# MissingLink.net
KiCad netlist of a schematic drawn in Altium Designer
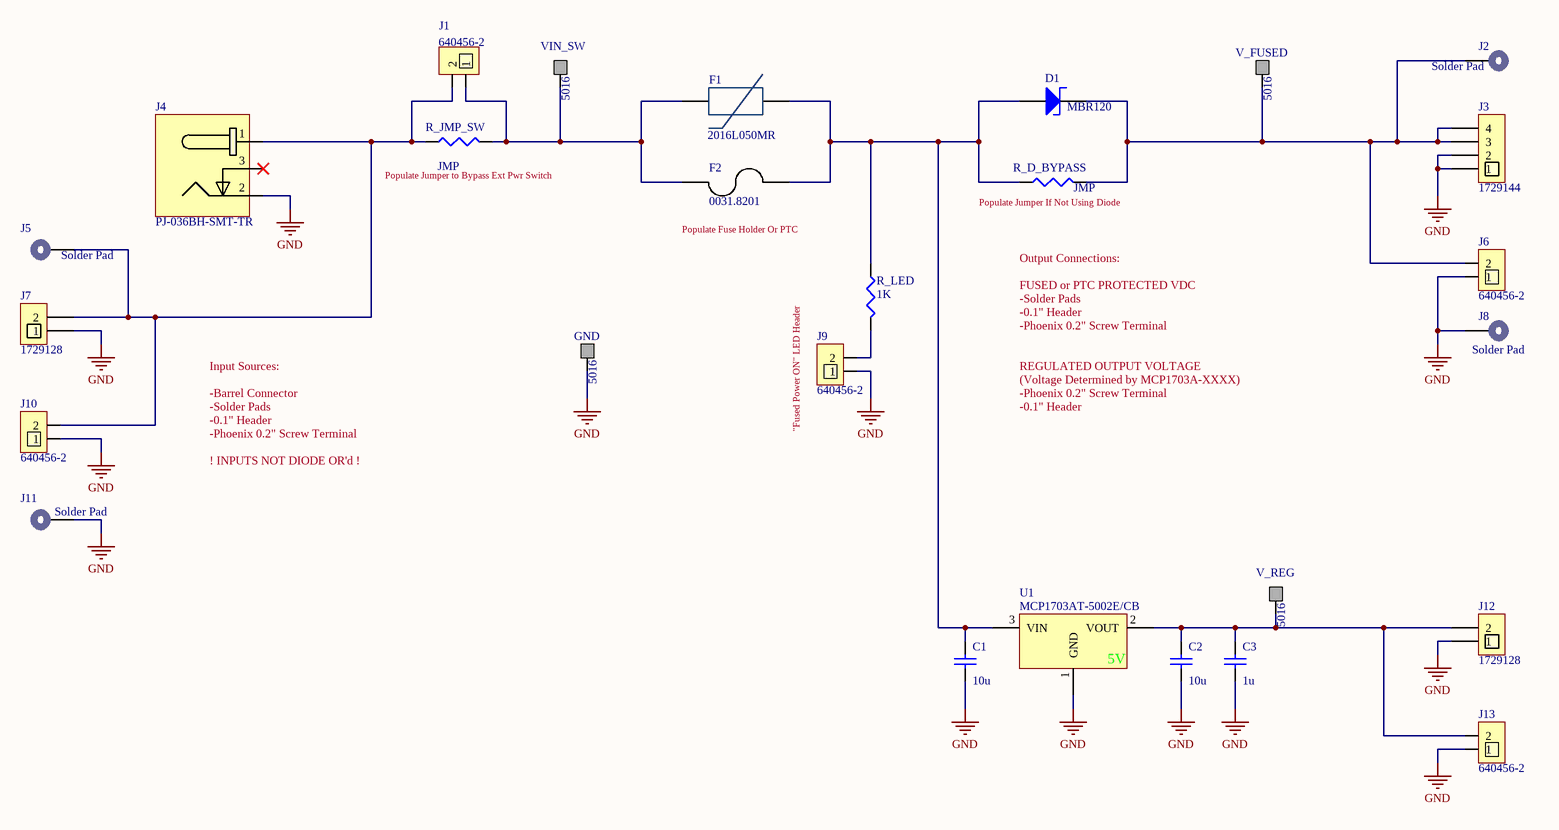
[diagram p0: MissingLink.SchDoc]

(export (version "E")
  (design (tool "Eeschema 10.0.6"))
  (components
    (comp (ref "C1")
      (value "10u")
      (footprint "C1206")
      (description "Capacitor (Semiconductor SIM Model)")
      (fields (field (name "Comment") "Cap Semi") (field (name "PUBLISHER") "Altium Limited"))
      (libsource (lib "Miscellaneous Devices") (part "Cap Semi"))
    )
    (comp (ref "C2")
      (value "10u")
      (footprint "C1206")
      (description "Capacitor (Semiconductor SIM Model)")
      (fields (field (name "Comment") "Cap Semi") (field (name "PUBLISHER") "Altium Limited"))
      (libsource (lib "Miscellaneous Devices") (part "Cap Semi"))
    )
    (comp (ref "C3")
      (value "1u")
      (footprint "C1206")
      (description "Capacitor (Semiconductor SIM Model)")
      (fields (field (name "Comment") "Cap Semi") (field (name "PUBLISHER") "Altium Limited"))
      (libsource (lib "Miscellaneous Devices") (part "Cap Semi"))
    )
    (comp (ref "D1")
      (value "Diode")
      (footprint "SOD-123FL")
      (description "DIODE SCHOTTKY 20V 1A SOD123FL")
      (fields
        (field (name "MANUFACTURER") "ON Semiconductor")
        (field (name "MANUFACTURER PART NUMBER") "MBR120")
      )
      (libsource (lib "Electric_Ray_Integrated_01SEPT2018") (part "MBR120"))
    )
    (comp (ref "F1")
      (value "2016L050MR")
      (footprint "PolyFuse_2016L")
      (description "600mA PTC")
      (fields (field (name "MANUFACTURER") "Littelfuse Inc."))
      (libsource (lib "Electric_Ray_Integrated_01SEPT2018") (part "PTC_2016L050MR_LITTELFUSE"))
    )
    (comp (ref "F2")
      (value "0031.8201")
      (footprint "0031.8201")
      (description "FUSE BLOK CARTRIDGE 500V 10A PCB")
      (fields (field (name "MANUFACTURER") "Schurter"))
      (libsource (lib "Electric_Ray_Integrated_01SEPT2018") (part "0031.8201"))
    )
    (comp (ref "GND")
      (value "5016")
      (footprint "5016")
      (description "PC TEST POINT COMPACT SMD")
      (fields (field (name "MANUFACTURER") "Keystone Electronics"))
      (libsource (lib "Electric_Ray_Integrated_01SEPT2018") (part "5016"))
    )
    (comp (ref "J1")
      (value "640456-2")
      (footprint "640456-2")
      (description "CONN HEADER VERT 2POS .100 TIN")
      (fields (field (name "MANUFACTURER") "TE Connectivity AMP Connectors"))
      (libsource (lib "") (part "640456-2_2"))
    )
    (comp (ref "J2")
      (value "Solder Pad")
      (footprint "61mil_Solder_Hole")
      (description "A Solderable Pad")
      (libsource (lib "Electric_Ray_Integrated_01SEPT2018") (part "Solderable_Hole"))
    )
    (comp (ref "J3")
      (value "1729144")
      (footprint "1729144_PHX_4")
      (description "CONN TERM BLOCK 4POS 5.08MM PCB")
      (fields (field (name "MANUFACTURER") "Phoenix Connect"))
      (libsource (lib "Electric_Ray_Integrated_01SEPT2018") (part "1729144"))
    )
    (comp (ref "J4")
      (value "PJ-036BH-SMT-TR")
      (footprint "PJ-036BH-SMT-TR")
      (description "CONN PWR JACK 2.5X5.5MM SOLDER")
      (fields (field (name "MANUFACTURER") "CUI"))
      (libsource (lib "Electric_Ray_Integrated_01SEPT2018") (part "PJ-036BH-SMT-TR"))
    )
    (comp (ref "J5")
      (value "Solder Pad")
      (footprint "61mil_Solder_Hole")
      (description "A Solderable Pad")
      (libsource (lib "Electric_Ray_Integrated_01SEPT2018") (part "Solderable_Hole"))
    )
    (comp (ref "J6")
      (value "640456-2")
      (footprint "640456-2")
      (description "CONN HEADER VERT 2POS .100 TIN")
      (fields (field (name "MANUFACTURER") "TE Connectivity AMP Connectors"))
      (libsource (lib "Electric_Ray_Integrated_01SEPT2018") (part "640456-2"))
    )
    (comp (ref "J7")
      (value "1729128")
      (footprint "1729128_PHX_2")
      (description "CONN TERM BLOCK 2POS 5.08MM PCB")
      (fields (field (name "MANUFACTURER") "Phoenix Connect"))
      (libsource (lib "Electric_Ray_Integrated_01SEPT2018") (part "1729128"))
    )
    (comp (ref "J8")
      (value "Solder Pad")
      (footprint "61mil_Solder_Hole")
      (description "A Solderable Pad")
      (libsource (lib "Electric_Ray_Integrated_01SEPT2018") (part "Solderable_Hole"))
    )
    (comp (ref "J9")
      (value "640456-2")
      (footprint "640456-2")
      (description "CONN HEADER VERT 2POS .100 TIN")
      (fields (field (name "MANUFACTURER") "TE Connectivity AMP Connectors"))
      (libsource (lib "") (part "640456-2_1"))
    )
    (comp (ref "J10")
      (value "640456-2")
      (footprint "640456-2")
      (description "CONN HEADER VERT 2POS .100 TIN")
      (fields (field (name "MANUFACTURER") "TE Connectivity AMP Connectors"))
      (libsource (lib "") (part "640456-2_1"))
    )
    (comp (ref "J11")
      (value "Solder Pad")
      (footprint "61mil_Solder_Hole")
      (description "A Solderable Pad")
      (libsource (lib "Electric_Ray_Integrated_01SEPT2018") (part "Solderable_Hole"))
    )
    (comp (ref "J12")
      (value "1729128")
      (footprint "1729128_PHX_2")
      (description "CONN TERM BLOCK 2POS 5.08MM PCB")
      (fields (field (name "MANUFACTURER") "Phoenix Connect"))
      (libsource (lib "") (part "1729128_1"))
    )
    (comp (ref "J13")
      (value "640456-2")
      (footprint "640456-2")
      (description "CONN HEADER VERT 2POS .100 TIN")
      (fields (field (name "MANUFACTURER") "TE Connectivity AMP Connectors"))
      (libsource (lib "Electric_Ray_Integrated_01SEPT2018") (part "640456-2"))
    )
    (comp (ref "R_D_BYPASS")
      (value "JMP")
      (footprint "Electric_Ray_Integrated_01SEPT2018:0805_L")
      (description "Resistor")
      (fields (field (name "Comment") "Res3") (field (name "PUBLISHER") "Altium Limited"))
      (libsource (lib "Miscellaneous Devices") (part "Res3"))
    )
    (comp (ref "R_JMP_SW")
      (value "JMP")
      (footprint "Electric_Ray_Integrated_01SEPT2018:0805_L")
      (description "Resistor")
      (fields (field (name "Comment") "Res3") (field (name "PUBLISHER") "Altium Limited"))
      (libsource (lib "Miscellaneous Devices") (part "Res3"))
    )
    (comp (ref "R_LED")
      (value "1K")
      (footprint "Electric_Ray_Integrated_01SEPT2018:0805_L")
      (description "Resistor")
      (fields (field (name "Comment") "Res3") (field (name "PUBLISHER") "Altium Limited"))
      (libsource (lib "Miscellaneous Devices") (part "Res3"))
    )
    (comp (ref "U1")
      (value "MCP1703AT-5002E/CB")
      (footprint "SOT-23A")
      (description "IC REG LINEAR 5V 250MA SOT23A-3")
      (fields (field (name "MANUFACTURER") "Microchip Technology"))
      (libsource (lib "Electric_Ray_Integrated_01SEPT2018") (part "MCP1703AT-5002E/CB"))
    )
    (comp (ref "VIN_SW")
      (value "5016")
      (footprint "5016")
      (description "PC TEST POINT COMPACT SMD")
      (fields (field (name "MANUFACTURER") "Keystone Electronics"))
      (libsource (lib "Electric_Ray_Integrated_01SEPT2018") (part "5016"))
    )
    (comp (ref "V_FUSED")
      (value "5016")
      (footprint "5016")
      (description "PC TEST POINT COMPACT SMD")
      (fields (field (name "MANUFACTURER") "Keystone Electronics"))
      (libsource (lib "Electric_Ray_Integrated_01SEPT2018") (part "5016"))
    )
    (comp (ref "V_REG")
      (value "5016")
      (footprint "5016")
      (description "PC TEST POINT COMPACT SMD")
      (fields (field (name "MANUFACTURER") "Keystone Electronics"))
      (libsource (lib "Electric_Ray_Integrated_01SEPT2018") (part "5016"))
    )
  )
  (nets
    (net (code "1") (name "GND") (class "Default")
      (node (ref "C1") (pin "1") (pinfunction "1_1") (pintype "passive"))
      (node (ref "C2") (pin "1") (pinfunction "1_1") (pintype "passive"))
      (node (ref "C3") (pin "1") (pinfunction "1_1") (pintype "passive"))
      (node (ref "GND") (pin "1") (pinfunction "1_1") (pintype "passive"))
      (node (ref "J10") (pin "1") (pinfunction "1_1") (pintype "passive"))
      (node (ref "J11") (pin "1") (pinfunction "1_1") (pintype "passive"))
      (node (ref "J12") (pin "1") (pinfunction "1_1") (pintype "passive"))
      (node (ref "J13") (pin "1") (pinfunction "1_1") (pintype "passive"))
      (node (ref "J3") (pin "1") (pinfunction "1_1") (pintype "passive"))
      (node (ref "J3") (pin "2") (pinfunction "2_2") (pintype "passive"))
      (node (ref "J4") (pin "2") (pinfunction "2_2") (pintype "passive"))
      (node (ref "J6") (pin "1") (pinfunction "1_1") (pintype "passive"))
      (node (ref "J7") (pin "1") (pinfunction "1_1") (pintype "passive"))
      (node (ref "J8") (pin "1") (pinfunction "1_1") (pintype "passive"))
      (node (ref "J9") (pin "1") (pinfunction "1_1") (pintype "passive"))
      (node (ref "U1") (pin "1") (pinfunction "GND_1") (pintype "passive"))
    )
    (net (code "2") (name "Net-(D1-PadK)") (class "Default")
      (node (ref "D1") (pin "K") (pinfunction "K_K") (pintype "passive"))
      (node (ref "J2") (pin "1") (pinfunction "1_1") (pintype "passive"))
      (node (ref "J3") (pin "3") (pinfunction "3_3") (pintype "passive"))
      (node (ref "J3") (pin "4") (pinfunction "4_4") (pintype "passive"))
      (node (ref "J6") (pin "2") (pinfunction "2_2") (pintype "passive"))
      (node (ref "R_D_BYPASS") (pin "2") (pinfunction "2_2") (pintype "passive"))
      (node (ref "V_FUSED") (pin "1") (pinfunction "1_1") (pintype "passive"))
    )
    (net (code "3") (name "Net-(F1-Pad1)") (class "Default")
      (node (ref "F1") (pin "1") (pinfunction "1_1") (pintype "passive"))
      (node (ref "F2") (pin "1") (pinfunction "1_1") (pintype "passive"))
      (node (ref "J1") (pin "1") (pinfunction "1_1") (pintype "passive"))
      (node (ref "R_JMP_SW") (pin "2") (pinfunction "2_2") (pintype "passive"))
      (node (ref "VIN_SW") (pin "1") (pinfunction "1_1") (pintype "passive"))
    )
    (net (code "4") (name "Net-(J1-Pad2)") (class "Default")
      (node (ref "J1") (pin "2") (pinfunction "2_2") (pintype "passive"))
      (node (ref "J10") (pin "2") (pinfunction "2_2") (pintype "passive"))
      (node (ref "J4") (pin "1") (pinfunction "1_1") (pintype "passive"))
      (node (ref "J5") (pin "1") (pinfunction "1_1") (pintype "passive"))
      (node (ref "J7") (pin "2") (pinfunction "2_2") (pintype "passive"))
      (node (ref "R_JMP_SW") (pin "1") (pinfunction "1_1") (pintype "passive"))
    )
    (net (code "5") (name "Net-(J9-Pad2)") (class "Default")
      (node (ref "J9") (pin "2") (pinfunction "2_2") (pintype "passive"))
      (node (ref "R_LED") (pin "1") (pinfunction "1_1") (pintype "passive"))
    )
    (net (code "6") (name "Net-(U1-VIN)") (class "Default")
      (node (ref "C1") (pin "2") (pinfunction "2_2") (pintype "passive"))
      (node (ref "D1") (pin "A") (pinfunction "A_A") (pintype "passive"))
      (node (ref "F1") (pin "2") (pinfunction "2_2") (pintype "passive"))
      (node (ref "F2") (pin "2") (pinfunction "2_2") (pintype "passive"))
      (node (ref "R_D_BYPASS") (pin "1") (pinfunction "1_1") (pintype "passive"))
      (node (ref "R_LED") (pin "2") (pinfunction "2_2") (pintype "passive"))
      (node (ref "U1") (pin "3") (pinfunction "VIN_3") (pintype "passive"))
    )
    (net (code "7") (name "Net-(U1-VOUT)") (class "Default")
      (node (ref "C2") (pin "2") (pinfunction "2_2") (pintype "passive"))
      (node (ref "C3") (pin "2") (pinfunction "2_2") (pintype "passive"))
      (node (ref "J12") (pin "2") (pinfunction "2_2") (pintype "passive"))
      (node (ref "J13") (pin "2") (pinfunction "2_2") (pintype "passive"))
      (node (ref "U1") (pin "2") (pinfunction "VOUT_2") (pintype "passive"))
      (node (ref "V_REG") (pin "1") (pinfunction "1_1") (pintype "passive"))
    )
    (net (code "8") (name "unconnected-(J4-Pad3)") (class "Default")
      (node (ref "J4") (pin "3") (pinfunction "3_3") (pintype "passive+no_connect"))
    )
  )
)
